# MPU.net
KiCad netlist of a schematic drawn in Altium Designer
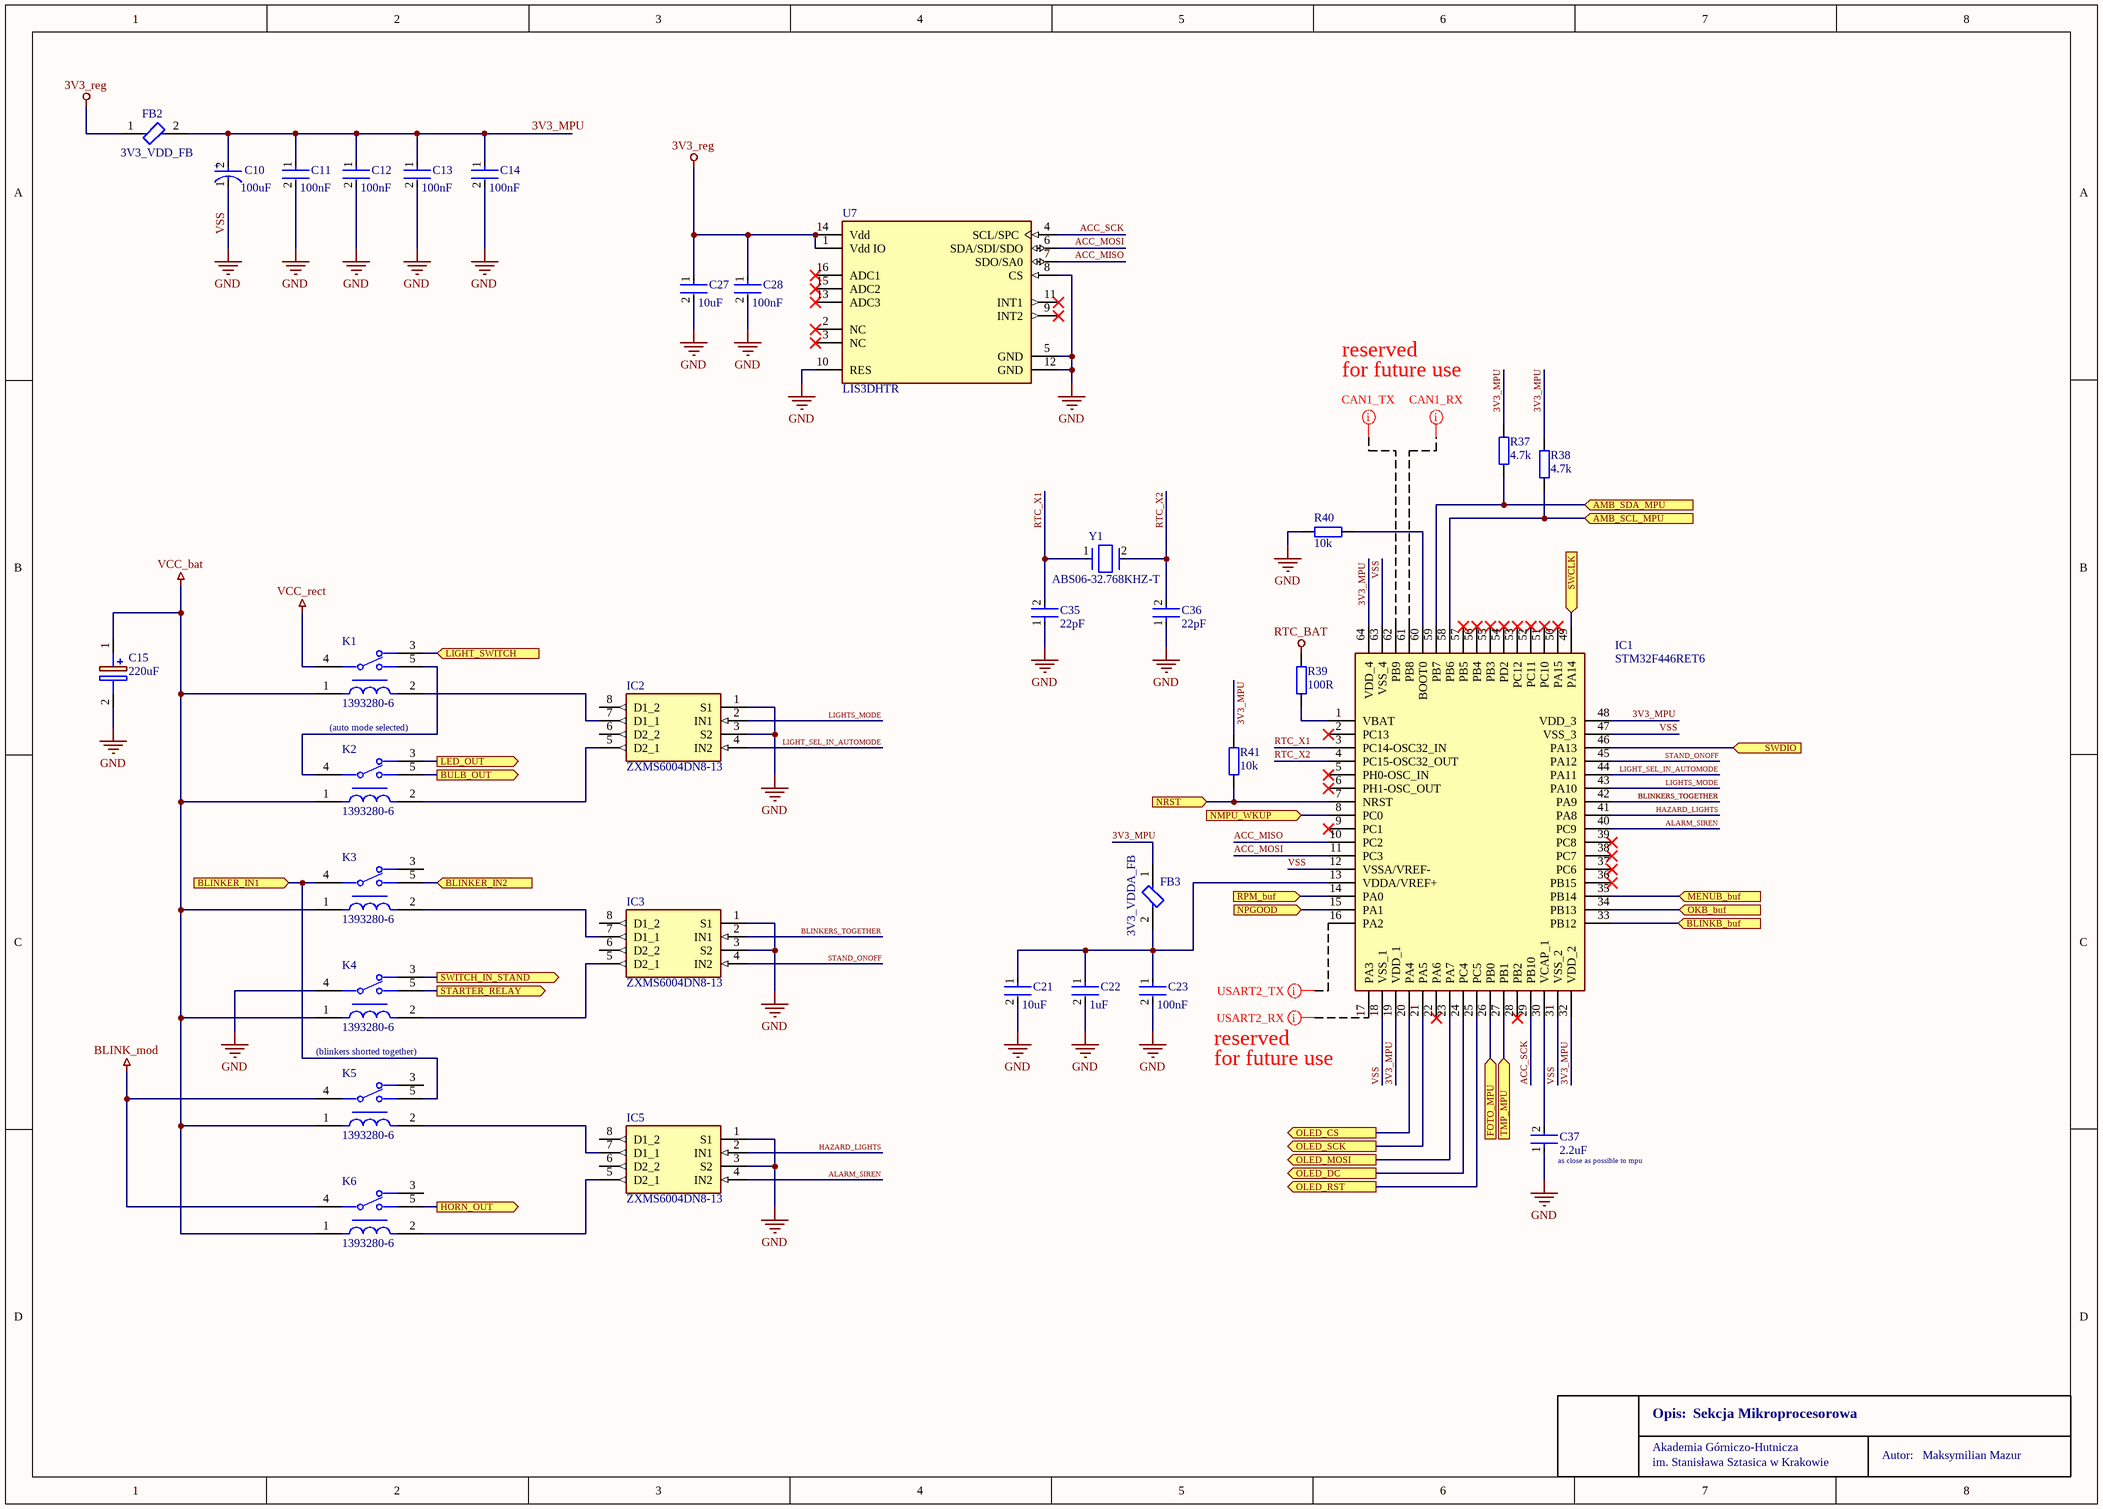
[diagram p0: MPU.SchDoc]

(export (version "E")
  (design (tool "Eeschema 10.0.6"))
  (components
    (comp (ref "C10")
      (value "100uF")
      (footprint "FP-TAJB-MFG")
      (description "100uF 6.3V  ±10% 1.7Ω 1210  SMD Tantalum Capacitor\r\nTAJB107K006RNJ")
      (fields (field (name "VOLTAGE") "6.3V") (field (name "TOLERANCE") "10%"))
      (libsource (lib "Altium Content Vault") (part "203bc49f2ac43e59fd269a8c329ed05"))
    )
    (comp (ref "C11")
      (value "100nF")
      (footprint "FP-CL10-IPC_A")
      (description "Cap Ceramic 100nF 10V X7R ±10% Pad SMD 0603 +125°C T/R")
      (fields (field (name "VOLTAGE") "50V") (field (name "TOLERANCE") "10%"))
      (libsource (lib "Altium Content Vault") (part "b4654b650e69147ec39a6b967a45e02"))
    )
    (comp (ref "C12")
      (value "100nF")
      (footprint "FP-CL10-IPC_A")
      (description "Cap Ceramic 100nF 10V X7R ±10% Pad SMD 0603 +125°C T/R")
      (fields (field (name "VOLTAGE") "50V") (field (name "TOLERANCE") "10%"))
      (libsource (lib "Altium Content Vault") (part "b4654b650e69147ec39a6b967a45e02"))
    )
    (comp (ref "C13")
      (value "100nF")
      (footprint "FP-CL10-IPC_A")
      (description "Cap Ceramic 100nF 10V X7R ±10% Pad SMD 0603 +125°C T/R")
      (fields (field (name "VOLTAGE") "50V") (field (name "TOLERANCE") "10%"))
      (libsource (lib "Altium Content Vault") (part "b4654b650e69147ec39a6b967a45e02"))
    )
    (comp (ref "C14")
      (value "100nF")
      (footprint "FP-CL10-IPC_A")
      (description "Cap Ceramic 100nF 10V X7R ±10% Pad SMD 0603 +125°C T/R")
      (fields (field (name "VOLTAGE") "50V") (field (name "TOLERANCE") "10%"))
      (libsource (lib "Altium Content Vault") (part "b4654b650e69147ec39a6b967a45e02"))
    )
    (comp (ref "C15")
      (value "220uF")
      (footprint "SamacSys:CAPAE660X810N")
      (description "Capacitor Polarised\r\n220uF 16V\r\n\r\nSC1C227M6L07KVR")
      (fields (field (name "MANUFACTURER_PART_NUMBER") "SC1C227M6L07KVR"))
      (libsource (lib "*") (part "SC1C227M6L07KVR"))
    )
    (comp (ref "C21")
      (value "10uF")
      (footprint "FP-CL10-IPC_A")
      (description "Cap Ceramic 10uF 10V X7R ±10% Pad SMD 0603 +125°C T/R")
      (fields (field (name "VOLTAGE") "50V") (field (name "TOLERANCE") "10%"))
      (libsource (lib "Altium Content Vault") (part "b4654b650e69147ec39a6b967a45e02"))
    )
    (comp (ref "C22")
      (value "1uF")
      (footprint "FP-CL10-IPC_A")
      (description "Cap Ceramic 1uF 10V X7R ±10% Pad SMD 0603 +125°C T/R")
      (fields (field (name "VOLTAGE") "50V") (field (name "TOLERANCE") "10%"))
      (libsource (lib "Altium Content Vault") (part "b4654b650e69147ec39a6b967a45e02"))
    )
    (comp (ref "C23")
      (value "100nF")
      (footprint "FP-CL10-IPC_A")
      (description "Cap Ceramic 100nF 10V X7R ±10% Pad SMD 0603 +125°C T/R")
      (fields (field (name "VOLTAGE") "50V") (field (name "TOLERANCE") "10%"))
      (libsource (lib "Altium Content Vault") (part "b4654b650e69147ec39a6b967a45e02"))
    )
    (comp (ref "C27")
      (value "10uF")
      (footprint "FP-CL10-IPC_A")
      (description "Cap Ceramic 10uF 10V X7R ±10% Pad SMD 0603 +125°C T/R")
      (fields (field (name "VOLTAGE") "50V") (field (name "TOLERANCE") "10%"))
      (libsource (lib "Altium Content Vault") (part "b4654b650e69147ec39a6b967a45e02"))
    )
    (comp (ref "C28")
      (value "100nF")
      (footprint "FP-CL10-IPC_A")
      (description "Cap Ceramic 100nF 10V X7R ±10% Pad SMD 0603 +125°C T/R")
      (fields (field (name "VOLTAGE") "50V") (field (name "TOLERANCE") "10%"))
      (libsource (lib "Altium Content Vault") (part "b4654b650e69147ec39a6b967a45e02"))
    )
    (comp (ref "C35")
      (value "22pF")
      (footprint "FP-CL10-IPC_A")
      (description "Cap Ceramic 22pF 25V SMD 0603")
      (fields (field (name "VOLTAGE") "50V") (field (name "TOLERANCE") "10%"))
      (libsource (lib "Altium Content Vault") (part "b4654b650e69147ec39a6b967a45e02"))
    )
    (comp (ref "C36")
      (value "22pF")
      (footprint "FP-CL10-IPC_A")
      (description "Cap Ceramic 22pF 25V SMD 0603")
      (fields (field (name "VOLTAGE") "50V") (field (name "TOLERANCE") "10%"))
      (libsource (lib "Altium Content Vault") (part "b4654b650e69147ec39a6b967a45e02"))
    )
    (comp (ref "C37")
      (value "2.2uF")
      (footprint "FP-CL10-IPC_A")
      (description "Cap Ceramic 2.2uF\r\nSMD 0603")
      (fields (field (name "VOLTAGE") "50V") (field (name "TOLERANCE") "10%"))
      (libsource (lib "Altium Content Vault") (part "b4654b650e69147ec39a6b967a45e02"))
    )
    (comp (ref "FB2")
      (value "3V3_VDD_FB")
      (footprint "FP-BLM18-0_15-t0_8-IPC_A")
      (description "Chip Ferrite Bead, 0603\r\nZ = 220, f = 100MHz")
      (fields (field (name "TOLERANCE") "25%"))
      (libsource (lib "Altium Content Vault") (part "5f30dd21d616792df468990f7003faa"))
    )
    (comp (ref "FB3")
      (value "3V3_VDDA_FB")
      (footprint "FP-BLM18-0_15-t0_8-IPC_A")
      (description "Chip Ferrite Bead, 0603\r\nZ = 220, f = 100MHz")
      (fields (field (name "TOLERANCE") "25%"))
      (libsource (lib "Altium Content Vault") (part "5f30dd21d616792df468990f7003faa"))
    )
    (comp (ref "IC1")
      (value "STM32F446RET6")
      (footprint "SamacSys:QFP50P1200X1200X160-64N")
      (description "Integrated Circuit")
      (fields (field (name "MOUSER PART NUMBER") "511-STM32F446RET6"))
      (libsource (lib "*") (part "STM32F446RET6"))
    )
    (comp (ref "IC2")
      (value "ZXMS6004DN8-13")
      (footprint "SamacSys:SOIC127P600X175-8N")
      (description "Integrated Circuit")
      (fields (field (name "MOUSER PART NUMBER") "621-ZXMS6004DN8-13"))
      (libsource (lib "*") (part "ZXMS6004DN8-13"))
    )
    (comp (ref "IC3")
      (value "ZXMS6004DN8-13")
      (footprint "SamacSys:SOIC127P600X175-8N")
      (description "Integrated Circuit")
      (fields (field (name "MOUSER PART NUMBER") "621-ZXMS6004DN8-13"))
      (libsource (lib "*") (part "ZXMS6004DN8-13"))
    )
    (comp (ref "IC5")
      (value "ZXMS6004DN8-13")
      (footprint "SamacSys:SOIC127P600X175-8N")
      (description "Integrated Circuit")
      (fields (field (name "MOUSER PART NUMBER") "621-ZXMS6004DN8-13"))
      (libsource (lib "*") (part "ZXMS6004DN8-13"))
    )
    (comp (ref "K1")
      (value "1393280-6")
      (footprint "FP-1393280-6-MFG")
      (description "Electromechanical Relay 12VDC 254Ohm 40A SPDT (12.9x12x9.9)mm THT Power Relay")
      (fields
        (field (name "MANUFACTURER") "TE Connectivity")
        (field (name "OCTOPART") "https://octopart.com/1393280-6-te+connectivity-45289632")
      )
      (libsource (lib "Altium Content Vault") (part "97f54bb7ca2bbb29dbc233e4f473642"))
    )
    (comp (ref "K2")
      (value "1393280-6")
      (footprint "FP-1393280-6-MFG")
      (description "Electromechanical Relay 12VDC 254Ohm 40A SPDT (12.9x12x9.9)mm THT Power Relay")
      (fields
        (field (name "MANUFACTURER") "TE Connectivity")
        (field (name "OCTOPART") "https://octopart.com/1393280-6-te+connectivity-45289632")
      )
      (libsource (lib "Altium Content Vault") (part "97f54bb7ca2bbb29dbc233e4f473642"))
    )
    (comp (ref "K3")
      (value "1393280-6")
      (footprint "FP-1393280-6-MFG")
      (description "Electromechanical Relay 12VDC 254Ohm 40A SPDT (12.9x12x9.9)mm THT Power Relay")
      (fields
        (field (name "MANUFACTURER") "TE Connectivity")
        (field (name "OCTOPART") "https://octopart.com/1393280-6-te+connectivity-45289632")
      )
      (libsource (lib "Altium Content Vault") (part "97f54bb7ca2bbb29dbc233e4f473642"))
    )
    (comp (ref "K4")
      (value "1393280-6")
      (footprint "FP-1393280-6-MFG")
      (description "Electromechanical Relay 12VDC 254Ohm 40A SPDT (12.9x12x9.9)mm THT Power Relay")
      (fields
        (field (name "MANUFACTURER") "TE Connectivity")
        (field (name "OCTOPART") "https://octopart.com/1393280-6-te+connectivity-45289632")
      )
      (libsource (lib "Altium Content Vault") (part "97f54bb7ca2bbb29dbc233e4f473642"))
    )
    (comp (ref "K5")
      (value "1393280-6")
      (footprint "FP-1393280-6-MFG")
      (description "Electromechanical Relay 12VDC 254Ohm 40A SPDT (12.9x12x9.9)mm THT Power Relay")
      (fields
        (field (name "MANUFACTURER") "TE Connectivity")
        (field (name "OCTOPART") "https://octopart.com/1393280-6-te+connectivity-45289632")
      )
      (libsource (lib "Altium Content Vault") (part "97f54bb7ca2bbb29dbc233e4f473642"))
    )
    (comp (ref "K6")
      (value "1393280-6")
      (footprint "FP-1393280-6-MFG")
      (description "Electromechanical Relay 12VDC 254Ohm 40A SPDT (12.9x12x9.9)mm THT Power Relay")
      (fields
        (field (name "MANUFACTURER") "TE Connectivity")
        (field (name "OCTOPART") "https://octopart.com/1393280-6-te+connectivity-45289632")
      )
      (libsource (lib "Altium Content Vault") (part "97f54bb7ca2bbb29dbc233e4f473642"))
    )
    (comp (ref "R37")
      (value "4.7k")
      (footprint "RES_0603")
      (description "Resistor SMD 0603")
      (libsource (lib "Schematic-Lib-PhilsLab") (part "RES_0603"))
    )
    (comp (ref "R38")
      (value "4.7k")
      (footprint "RES_0603")
      (description "Resistor SMD 0603")
      (libsource (lib "Schematic-Lib-PhilsLab") (part "RES_0603"))
    )
    (comp (ref "R39")
      (value "100R")
      (footprint "RES_0603")
      (description "Resistor SMD 0603")
      (libsource (lib "Schematic-Lib-PhilsLab") (part "RES_0603"))
    )
    (comp (ref "R40")
      (value "10k")
      (footprint "RES_0603")
      (description "Resistor SMD 0603")
      (libsource (lib "Schematic-Lib-PhilsLab") (part "RES_0603"))
    )
    (comp (ref "R41")
      (value "10k")
      (footprint "RES_0603")
      (description "Resistor SMD 0603")
      (libsource (lib "Schematic-Lib-PhilsLab") (part "RES_0603"))
    )
    (comp (ref "U7")
      (value "LIS3DHTR")
      (footprint "FP-LGA-16-7983231-MFG")
      (description "ACCEL 2-16G I2C/SPI 16LGA")
      (libsource (lib "Altium Content Vault") (part "1e4772b22d749da4b53766bc623c8dd"))
    )
    (comp (ref "Y1")
      (value "ABS06-32.768KHZ-T")
      (footprint "FP-ABS06-MFG")
      (description "Crystal 32.768kHz ±20ppm (Tol) 12.5pF FUND 90kΩ 2-Pin Mini-CSMD T/R")
      (fields (field (name "TOLERANCE") "20ppm"))
      (libsource (lib "Altium Content Vault") (part "c23a69dc6c9e2f18f2079038eb95dd1"))
    )
  )
  (nets
    (net (code "1") (name "/3V3_MPU") (class "Default")
      (node (ref "C10") (pin "2") (pinfunction "A_2") (pintype "passive"))
      (node (ref "C11") (pin "1") (pinfunction "1_1") (pintype "passive"))
      (node (ref "C12") (pin "1") (pinfunction "1_1") (pintype "passive"))
      (node (ref "C13") (pin "1") (pinfunction "1_1") (pintype "passive"))
      (node (ref "C14") (pin "1") (pinfunction "1_1") (pintype "passive"))
      (node (ref "FB2") (pin "2") (pinfunction "2_2") (pintype "passive"))
      (node (ref "FB3") (pin "1") (pinfunction "1_1") (pintype "passive"))
      (node (ref "IC1") (pin "19") (pinfunction "VDD_1_19") (pintype "passive"))
      (node (ref "IC1") (pin "32") (pinfunction "VDD_2_32") (pintype "passive"))
      (node (ref "IC1") (pin "48") (pinfunction "VDD_3_48") (pintype "passive"))
      (node (ref "IC1") (pin "64") (pinfunction "VDD_4_64") (pintype "passive"))
      (node (ref "R37") (pin "1") (pinfunction "1_1") (pintype "passive"))
      (node (ref "R38") (pin "1") (pinfunction "1_1") (pintype "passive"))
      (node (ref "R41") (pin "1") (pinfunction "1_1") (pintype "passive"))
    )
    (net (code "2") (name "/ACC_MISO") (class "Default")
      (node (ref "IC1") (pin "10") (pinfunction "PC2_10") (pintype "passive"))
      (node (ref "U7") (pin "7") (pinfunction "SDO/SA0_7") (pintype "bidirectional"))
    )
    (net (code "3") (name "/ACC_MOSI") (class "Default")
      (node (ref "IC1") (pin "11") (pinfunction "PC3_11") (pintype "passive"))
      (node (ref "U7") (pin "6") (pinfunction "SDA/SDI/SDO_6") (pintype "bidirectional"))
    )
    (net (code "4") (name "/ACC_SCK") (class "Default")
      (node (ref "IC1") (pin "29") (pinfunction "PB10_29") (pintype "passive"))
      (node (ref "U7") (pin "4") (pinfunction "SCL/SPC_4") (pintype "input"))
    )
    (net (code "5") (name "/ALARM_SIREN") (class "Default")
      (node (ref "IC1") (pin "40") (pinfunction "PC9_40") (pintype "passive"))
      (node (ref "IC5") (pin "4") (pinfunction "IN2_4") (pintype "input"))
    )
    (net (code "6") (name "/AMB_SCL_MPU") (class "Default")
      (node (ref "IC1") (pin "58") (pinfunction "PB6_58") (pintype "passive"))
      (node (ref "R38") (pin "2") (pinfunction "2_2") (pintype "passive"))
    )
    (net (code "7") (name "/AMB_SDA_MPU") (class "Default")
      (node (ref "IC1") (pin "59") (pinfunction "PB7_59") (pintype "passive"))
      (node (ref "R37") (pin "2") (pinfunction "2_2") (pintype "passive"))
    )
    (net (code "8") (name "/BLINKB_buf") (class "Default")
      (node (ref "IC1") (pin "33") (pinfunction "PB12_33") (pintype "passive"))
    )
    (net (code "9") (name "/BLINKERS_TOGETHER") (class "Default")
      (node (ref "IC1") (pin "42") (pinfunction "PA9_42") (pintype "passive"))
      (node (ref "IC3") (pin "2") (pinfunction "IN1_2") (pintype "input"))
    )
    (net (code "10") (name "/BLINKER_IN1") (class "Default")
      (node (ref "K3") (pin "4") (pinfunction "4_4") (pintype "passive"))
      (node (ref "K5") (pin "5") (pinfunction "5_5") (pintype "passive"))
    )
    (net (code "11") (name "/BLINKER_IN2") (class "Default")
      (node (ref "K3") (pin "5") (pinfunction "5_5") (pintype "passive"))
    )
    (net (code "12") (name "/BULB_OUT") (class "Default")
      (node (ref "K2") (pin "5") (pinfunction "5_5") (pintype "passive"))
    )
    (net (code "13") (name "/FOTO_MPU") (class "Default")
      (node (ref "IC1") (pin "26") (pinfunction "PB0_26") (pintype "passive"))
    )
    (net (code "14") (name "/HAZARD_LIGHTS") (class "Default")
      (node (ref "IC1") (pin "41") (pinfunction "PA8_41") (pintype "passive"))
      (node (ref "IC5") (pin "2") (pinfunction "IN1_2") (pintype "input"))
    )
    (net (code "15") (name "/HORN_OUT") (class "Default")
      (node (ref "K6") (pin "5") (pinfunction "5_5") (pintype "passive"))
    )
    (net (code "16") (name "/LED_OUT") (class "Default")
      (node (ref "K2") (pin "3") (pinfunction "3_3") (pintype "passive"))
    )
    (net (code "17") (name "/LIGHTS_MODE") (class "Default")
      (node (ref "IC1") (pin "43") (pinfunction "PA10_43") (pintype "passive"))
      (node (ref "IC2") (pin "2") (pinfunction "IN1_2") (pintype "input"))
    )
    (net (code "18") (name "/LIGHT_SEL_IN_AUTOMODE") (class "Default")
      (node (ref "IC1") (pin "44") (pinfunction "PA11_44") (pintype "passive"))
      (node (ref "IC2") (pin "4") (pinfunction "IN2_4") (pintype "input"))
    )
    (net (code "19") (name "/LIGHT_SWITCH") (class "Default")
      (node (ref "K1") (pin "3") (pinfunction "3_3") (pintype "passive"))
    )
    (net (code "20") (name "/MENUB_buf") (class "Default")
      (node (ref "IC1") (pin "35") (pinfunction "PB14_35") (pintype "passive"))
    )
    (net (code "21") (name "/NMPU_WKUP") (class "Default")
      (node (ref "IC1") (pin "8") (pinfunction "PC0_8") (pintype "passive"))
    )
    (net (code "22") (name "/NPGOOD") (class "Default")
      (node (ref "IC1") (pin "15") (pinfunction "PA1_15") (pintype "passive"))
    )
    (net (code "23") (name "/NRST") (class "Default")
      (node (ref "IC1") (pin "7") (pinfunction "NRST_7") (pintype "passive"))
      (node (ref "R41") (pin "2") (pinfunction "2_2") (pintype "passive"))
    )
    (net (code "24") (name "/OKB_buf") (class "Default")
      (node (ref "IC1") (pin "34") (pinfunction "PB13_34") (pintype "passive"))
    )
    (net (code "25") (name "/OLED_CS") (class "Default")
      (node (ref "IC1") (pin "20") (pinfunction "PA4_20") (pintype "passive"))
    )
    (net (code "26") (name "/OLED_DC") (class "Default")
      (node (ref "IC1") (pin "24") (pinfunction "PC4_24") (pintype "passive"))
    )
    (net (code "27") (name "/OLED_MOSI") (class "Default")
      (node (ref "IC1") (pin "23") (pinfunction "PA7_23") (pintype "passive"))
    )
    (net (code "28") (name "/OLED_RST") (class "Default")
      (node (ref "IC1") (pin "25") (pinfunction "PC5_25") (pintype "passive"))
    )
    (net (code "29") (name "/OLED_SCK") (class "Default")
      (node (ref "IC1") (pin "21") (pinfunction "PA5_21") (pintype "passive"))
    )
    (net (code "30") (name "/RPM_buf") (class "Default")
      (node (ref "IC1") (pin "14") (pinfunction "PA0_14") (pintype "passive"))
    )
    (net (code "31") (name "/RTC_X1") (class "Default")
      (node (ref "C35") (pin "2") (pinfunction "2_2") (pintype "passive"))
      (node (ref "IC1") (pin "3") (pinfunction "PC14-OSC32_IN_3") (pintype "passive"))
      (node (ref "Y1") (pin "1") (pinfunction "1_1") (pintype "passive"))
    )
    (net (code "32") (name "/RTC_X2") (class "Default")
      (node (ref "C36") (pin "2") (pinfunction "2_2") (pintype "passive"))
      (node (ref "IC1") (pin "4") (pinfunction "PC15-OSC32_OUT_4") (pintype "passive"))
      (node (ref "Y1") (pin "2") (pinfunction "2_2") (pintype "passive"))
    )
    (net (code "33") (name "/STAND_ONOFF") (class "Default")
      (node (ref "IC1") (pin "45") (pinfunction "PA12_45") (pintype "passive"))
      (node (ref "IC3") (pin "4") (pinfunction "IN2_4") (pintype "input"))
    )
    (net (code "34") (name "/STARTER_RELAY") (class "Default")
      (node (ref "K4") (pin "5") (pinfunction "5_5") (pintype "passive"))
    )
    (net (code "35") (name "/SWCLK") (class "Default")
      (node (ref "IC1") (pin "49") (pinfunction "PA14_49") (pintype "passive"))
    )
    (net (code "36") (name "/SWDIO") (class "Default")
      (node (ref "IC1") (pin "46") (pinfunction "PA13_46") (pintype "passive"))
    )
    (net (code "37") (name "/SWITCH_IN_STAND") (class "Default")
      (node (ref "K4") (pin "3") (pinfunction "3_3") (pintype "passive"))
    )
    (net (code "38") (name "/TMP_MPU") (class "Default")
      (node (ref "IC1") (pin "27") (pinfunction "PB1_27") (pintype "passive"))
    )
    (net (code "39") (name "3V3_reg") (class "Default")
      (node (ref "C27") (pin "1") (pinfunction "1_1") (pintype "passive"))
      (node (ref "C28") (pin "1") (pinfunction "1_1") (pintype "passive"))
      (node (ref "FB2") (pin "1") (pinfunction "1_1") (pintype "passive"))
      (node (ref "U7") (pin "1") (pinfunction "Vdd_IO_1") (pintype "power_in"))
      (node (ref "U7") (pin "14") (pinfunction "Vdd_14") (pintype "power_in"))
    )
    (net (code "40") (name "BLINK_mod") (class "Default")
      (node (ref "K5") (pin "4") (pinfunction "4_4") (pintype "passive"))
      (node (ref "K6") (pin "4") (pinfunction "4_4") (pintype "passive"))
    )
    (net (code "41") (name "GND") (class "Default")
      (node (ref "C10") (pin "1") (pinfunction "C_1") (pintype "passive"))
      (node (ref "C11") (pin "2") (pinfunction "2_2") (pintype "passive"))
      (node (ref "C12") (pin "2") (pinfunction "2_2") (pintype "passive"))
      (node (ref "C13") (pin "2") (pinfunction "2_2") (pintype "passive"))
      (node (ref "C14") (pin "2") (pinfunction "2_2") (pintype "passive"))
      (node (ref "C15") (pin "2") (pinfunction "-_2") (pintype "passive"))
      (node (ref "C21") (pin "2") (pinfunction "2_2") (pintype "passive"))
      (node (ref "C22") (pin "2") (pinfunction "2_2") (pintype "passive"))
      (node (ref "C23") (pin "2") (pinfunction "2_2") (pintype "passive"))
      (node (ref "C27") (pin "2") (pinfunction "2_2") (pintype "passive"))
      (node (ref "C28") (pin "2") (pinfunction "2_2") (pintype "passive"))
      (node (ref "C35") (pin "1") (pinfunction "1_1") (pintype "passive"))
      (node (ref "C36") (pin "1") (pinfunction "1_1") (pintype "passive"))
      (node (ref "C37") (pin "1") (pinfunction "1_1") (pintype "passive"))
      (node (ref "IC1") (pin "12") (pinfunction "VSSA/VREF-_12") (pintype "passive"))
      (node (ref "IC1") (pin "18") (pinfunction "VSS_1_18") (pintype "passive"))
      (node (ref "IC1") (pin "31") (pinfunction "VSS_2_31") (pintype "passive"))
      (node (ref "IC1") (pin "47") (pinfunction "VSS_3_47") (pintype "passive"))
      (node (ref "IC1") (pin "63") (pinfunction "VSS_4_63") (pintype "passive"))
      (node (ref "IC2") (pin "1") (pinfunction "S1_1") (pintype "power_in"))
      (node (ref "IC2") (pin "3") (pinfunction "S2_3") (pintype "power_in"))
      (node (ref "IC3") (pin "1") (pinfunction "S1_1") (pintype "power_in"))
      (node (ref "IC3") (pin "3") (pinfunction "S2_3") (pintype "power_in"))
      (node (ref "IC5") (pin "1") (pinfunction "S1_1") (pintype "power_in"))
      (node (ref "IC5") (pin "3") (pinfunction "S2_3") (pintype "power_in"))
      (node (ref "K4") (pin "4") (pinfunction "4_4") (pintype "passive"))
      (node (ref "R40") (pin "1") (pinfunction "1_1") (pintype "passive"))
      (node (ref "U7") (pin "10") (pinfunction "RES_10") (pintype "passive"))
      (node (ref "U7") (pin "12") (pinfunction "GND_12") (pintype "power_in"))
      (node (ref "U7") (pin "5") (pinfunction "GND_5") (pintype "power_in"))
      (node (ref "U7") (pin "8") (pinfunction "CS_8") (pintype "input"))
    )
    (net (code "42") (name "Net-(IC1-BOOT0)") (class "Default")
      (node (ref "IC1") (pin "60") (pinfunction "BOOT0_60") (pintype "passive"))
      (node (ref "R40") (pin "2") (pinfunction "2_2") (pintype "passive"))
    )
    (net (code "43") (name "Net-(IC1-VBAT)") (class "Default")
      (node (ref "IC1") (pin "1") (pinfunction "VBAT_1") (pintype "passive"))
      (node (ref "R39") (pin "2") (pinfunction "2_2") (pintype "passive"))
    )
    (net (code "44") (name "Net-(IC1-VCAP_1)") (class "Default")
      (node (ref "C37") (pin "2") (pinfunction "2_2") (pintype "passive"))
      (node (ref "IC1") (pin "30") (pinfunction "VCAP_1_30") (pintype "passive"))
    )
    (net (code "45") (name "Net-(IC1-VDDA{slash}VREF+)") (class "Default")
      (node (ref "C21") (pin "1") (pinfunction "1_1") (pintype "passive"))
      (node (ref "C22") (pin "1") (pinfunction "1_1") (pintype "passive"))
      (node (ref "C23") (pin "1") (pinfunction "1_1") (pintype "passive"))
      (node (ref "FB3") (pin "2") (pinfunction "2_2") (pintype "passive"))
      (node (ref "IC1") (pin "13") (pinfunction "VDDA/VREF+_13") (pintype "passive"))
    )
    (net (code "46") (name "Net-(IC2-D1_1)") (class "Default")
      (node (ref "IC2") (pin "7") (pinfunction "D1_1_7") (pintype "output"))
      (node (ref "K1") (pin "2") (pinfunction "2_2") (pintype "passive"))
    )
    (net (code "47") (name "Net-(IC2-D2_1)") (class "Default")
      (node (ref "IC2") (pin "5") (pinfunction "D2_1_5") (pintype "output"))
      (node (ref "K2") (pin "2") (pinfunction "2_2") (pintype "passive"))
    )
    (net (code "48") (name "Net-(IC3-D1_1)") (class "Default")
      (node (ref "IC3") (pin "7") (pinfunction "D1_1_7") (pintype "output"))
      (node (ref "K3") (pin "2") (pinfunction "2_2") (pintype "passive"))
    )
    (net (code "49") (name "Net-(IC3-D2_1)") (class "Default")
      (node (ref "IC3") (pin "5") (pinfunction "D2_1_5") (pintype "output"))
      (node (ref "K4") (pin "2") (pinfunction "2_2") (pintype "passive"))
    )
    (net (code "50") (name "Net-(IC5-D1_1)") (class "Default")
      (node (ref "IC5") (pin "7") (pinfunction "D1_1_7") (pintype "output"))
      (node (ref "K5") (pin "2") (pinfunction "2_2") (pintype "passive"))
    )
    (net (code "51") (name "Net-(IC5-D2_1)") (class "Default")
      (node (ref "IC5") (pin "5") (pinfunction "D2_1_5") (pintype "output"))
      (node (ref "K6") (pin "2") (pinfunction "2_2") (pintype "passive"))
    )
    (net (code "52") (name "Net-(K1-Pad5)") (class "Default")
      (node (ref "K1") (pin "5") (pinfunction "5_5") (pintype "passive"))
      (node (ref "K2") (pin "4") (pinfunction "4_4") (pintype "passive"))
    )
    (net (code "53") (name "RTC_BAT") (class "Default")
      (node (ref "R39") (pin "1") (pinfunction "1_1") (pintype "passive"))
    )
    (net (code "54") (name "VCC_bat") (class "Default")
      (node (ref "C15") (pin "1") (pinfunction "+_1") (pintype "passive"))
      (node (ref "K1") (pin "1") (pinfunction "1_1") (pintype "passive"))
      (node (ref "K2") (pin "1") (pinfunction "1_1") (pintype "passive"))
      (node (ref "K3") (pin "1") (pinfunction "1_1") (pintype "passive"))
      (node (ref "K4") (pin "1") (pinfunction "1_1") (pintype "passive"))
      (node (ref "K5") (pin "1") (pinfunction "1_1") (pintype "passive"))
      (node (ref "K6") (pin "1") (pinfunction "1_1") (pintype "passive"))
    )
    (net (code "55") (name "VCC_rect") (class "Default")
      (node (ref "K1") (pin "4") (pinfunction "4_4") (pintype "passive"))
    )
    (net (code "56") (name "unconnected-(IC1-PA2-Pad16)") (class "Default")
      (node (ref "IC1") (pin "16") (pinfunction "PA2_16") (pintype "passive"))
    )
    (net (code "57") (name "unconnected-(IC1-PA3-Pad17)") (class "Default")
      (node (ref "IC1") (pin "17") (pinfunction "PA3_17") (pintype "passive"))
    )
    (net (code "58") (name "unconnected-(IC1-PA6-Pad22)") (class "Default")
      (node (ref "IC1") (pin "22") (pinfunction "PA6_22") (pintype "passive+no_connect"))
    )
    (net (code "59") (name "unconnected-(IC1-PA15-Pad50)") (class "Default")
      (node (ref "IC1") (pin "50") (pinfunction "PA15_50") (pintype "passive+no_connect"))
    )
    (net (code "60") (name "unconnected-(IC1-PB2-Pad28)") (class "Default")
      (node (ref "IC1") (pin "28") (pinfunction "PB2_28") (pintype "passive+no_connect"))
    )
    (net (code "61") (name "unconnected-(IC1-PB3-Pad55)") (class "Default")
      (node (ref "IC1") (pin "55") (pinfunction "PB3_55") (pintype "passive+no_connect"))
    )
    (net (code "62") (name "unconnected-(IC1-PB4-Pad56)") (class "Default")
      (node (ref "IC1") (pin "56") (pinfunction "PB4_56") (pintype "passive+no_connect"))
    )
    (net (code "63") (name "unconnected-(IC1-PB5-Pad57)") (class "Default")
      (node (ref "IC1") (pin "57") (pinfunction "PB5_57") (pintype "passive+no_connect"))
    )
    (net (code "64") (name "unconnected-(IC1-PB8-Pad61)") (class "Default")
      (node (ref "IC1") (pin "61") (pinfunction "PB8_61") (pintype "passive"))
    )
    (net (code "65") (name "unconnected-(IC1-PB9-Pad62)") (class "Default")
      (node (ref "IC1") (pin "62") (pinfunction "PB9_62") (pintype "passive"))
    )
    (net (code "66") (name "unconnected-(IC1-PB15-Pad36)") (class "Default")
      (node (ref "IC1") (pin "36") (pinfunction "PB15_36") (pintype "passive+no_connect"))
    )
    (net (code "67") (name "unconnected-(IC1-PC1-Pad9)") (class "Default")
      (node (ref "IC1") (pin "9") (pinfunction "PC1_9") (pintype "passive+no_connect"))
    )
    (net (code "68") (name "unconnected-(IC1-PC6-Pad37)") (class "Default")
      (node (ref "IC1") (pin "37") (pinfunction "PC6_37") (pintype "passive+no_connect"))
    )
    (net (code "69") (name "unconnected-(IC1-PC7-Pad38)") (class "Default")
      (node (ref "IC1") (pin "38") (pinfunction "PC7_38") (pintype "passive+no_connect"))
    )
    (net (code "70") (name "unconnected-(IC1-PC8-Pad39)") (class "Default")
      (node (ref "IC1") (pin "39") (pinfunction "PC8_39") (pintype "passive+no_connect"))
    )
    (net (code "71") (name "unconnected-(IC1-PC10-Pad51)") (class "Default")
      (node (ref "IC1") (pin "51") (pinfunction "PC10_51") (pintype "passive+no_connect"))
    )
    (net (code "72") (name "unconnected-(IC1-PC11-Pad52)") (class "Default")
      (node (ref "IC1") (pin "52") (pinfunction "PC11_52") (pintype "passive+no_connect"))
    )
    (net (code "73") (name "unconnected-(IC1-PC12-Pad53)") (class "Default")
      (node (ref "IC1") (pin "53") (pinfunction "PC12_53") (pintype "passive+no_connect"))
    )
    (net (code "74") (name "unconnected-(IC1-PC13-Pad2)") (class "Default")
      (node (ref "IC1") (pin "2") (pinfunction "PC13_2") (pintype "passive+no_connect"))
    )
    (net (code "75") (name "unconnected-(IC1-PD2-Pad54)") (class "Default")
      (node (ref "IC1") (pin "54") (pinfunction "PD2_54") (pintype "passive+no_connect"))
    )
    (net (code "76") (name "unconnected-(IC1-PH0-OSC_IN-Pad5)") (class "Default")
      (node (ref "IC1") (pin "5") (pinfunction "PH0-OSC_IN_5") (pintype "passive+no_connect"))
    )
    (net (code "77") (name "unconnected-(IC1-PH1-OSC_OUT-Pad6)") (class "Default")
      (node (ref "IC1") (pin "6") (pinfunction "PH1-OSC_OUT_6") (pintype "passive+no_connect"))
    )
    (net (code "78") (name "unconnected-(IC2-D1_2-Pad8)") (class "Default")
      (node (ref "IC2") (pin "8") (pinfunction "D1_2_8") (pintype "output"))
    )
    (net (code "79") (name "unconnected-(IC2-D2_2-Pad6)") (class "Default")
      (node (ref "IC2") (pin "6") (pinfunction "D2_2_6") (pintype "output"))
    )
    (net (code "80") (name "unconnected-(IC3-D1_2-Pad8)") (class "Default")
      (node (ref "IC3") (pin "8") (pinfunction "D1_2_8") (pintype "output"))
    )
    (net (code "81") (name "unconnected-(IC3-D2_2-Pad6)") (class "Default")
      (node (ref "IC3") (pin "6") (pinfunction "D2_2_6") (pintype "output"))
    )
    (net (code "82") (name "unconnected-(IC5-D1_2-Pad8)") (class "Default")
      (node (ref "IC5") (pin "8") (pinfunction "D1_2_8") (pintype "output"))
    )
    (net (code "83") (name "unconnected-(IC5-D2_2-Pad6)") (class "Default")
      (node (ref "IC5") (pin "6") (pinfunction "D2_2_6") (pintype "output"))
    )
    (net (code "84") (name "unconnected-(K3-Pad3)") (class "Default")
      (node (ref "K3") (pin "3") (pinfunction "3_3") (pintype "passive"))
    )
    (net (code "85") (name "unconnected-(K5-Pad3)") (class "Default")
      (node (ref "K5") (pin "3") (pinfunction "3_3") (pintype "passive"))
    )
    (net (code "86") (name "unconnected-(K6-Pad3)") (class "Default")
      (node (ref "K6") (pin "3") (pinfunction "3_3") (pintype "passive"))
    )
    (net (code "87") (name "unconnected-(U7-ADC1-Pad16)") (class "Default")
      (node (ref "U7") (pin "16") (pinfunction "ADC1_16") (pintype "passive+no_connect"))
    )
    (net (code "88") (name "unconnected-(U7-ADC2-Pad15)") (class "Default")
      (node (ref "U7") (pin "15") (pinfunction "ADC2_15") (pintype "passive+no_connect"))
    )
    (net (code "89") (name "unconnected-(U7-ADC3-Pad13)") (class "Default")
      (node (ref "U7") (pin "13") (pinfunction "ADC3_13") (pintype "passive+no_connect"))
    )
    (net (code "90") (name "unconnected-(U7-INT1-Pad11)") (class "Default")
      (node (ref "U7") (pin "11") (pinfunction "INT1_11") (pintype "output+no_connect"))
    )
    (net (code "91") (name "unconnected-(U7-INT2-Pad9)") (class "Default")
      (node (ref "U7") (pin "9") (pinfunction "INT2_9") (pintype "output+no_connect"))
    )
    (net (code "92") (name "unconnected-(U7-NC-Pad2)") (class "Default")
      (node (ref "U7") (pin "2") (pinfunction "NC_2") (pintype "passive+no_connect"))
    )
    (net (code "93") (name "unconnected-(U7-NC-Pad3)") (class "Default")
      (node (ref "U7") (pin "3") (pinfunction "NC_3") (pintype "passive+no_connect"))
    )
  )
)
